# Connectors.net
KiCad netlist of a schematic drawn in Altium Designer
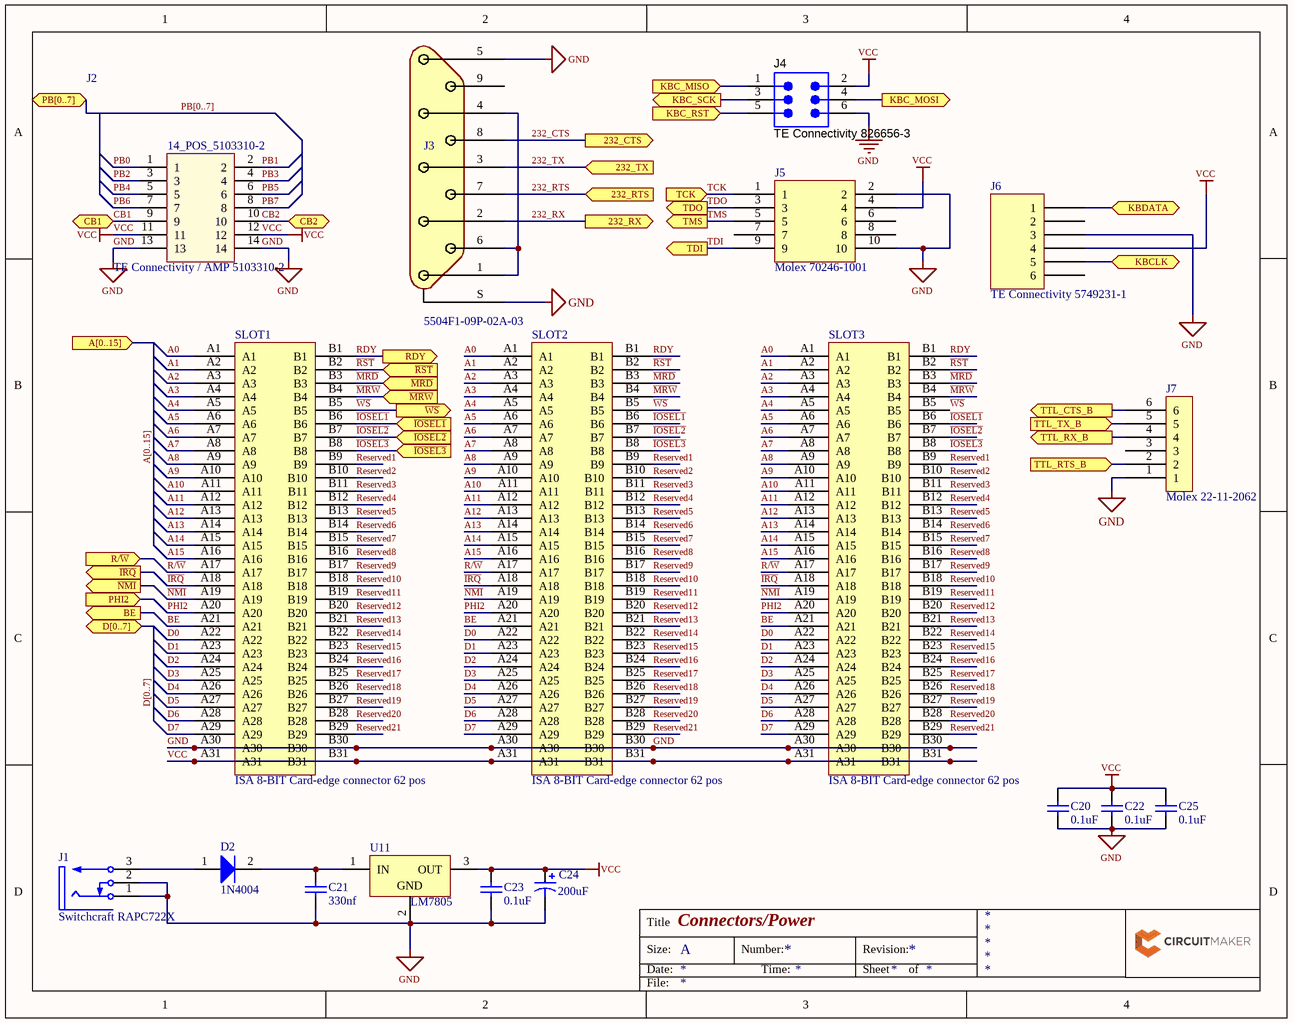
[diagram p0: Connectors.SchDoc]

(export (version "E")
  (design (tool "Eeschema 10.0.6"))
  (components
    (comp (ref "C20")
      (value "0.1uF")
      (footprint "CAPC1608X90X35NL15T15")
      (description "0603 0.1uF Capacitor")
      (libsource (lib "CommunityVault") (part "CAP-2"))
    )
    (comp (ref "C21")
      (value "330nf")
      (footprint "CAPC1608X90X35LL15T15")
      (description "CAP CER 0.33UF 16V 10% X5R 0603")
      (libsource (lib "CommunityVault") (part "CAP-2"))
    )
    (comp (ref "C22")
      (value "0.1uF")
      (footprint "CAPC1608X90X35NL15T15")
      (description "0603 0.1uF Capacitor")
      (libsource (lib "CommunityVault") (part "CAP-2"))
    )
    (comp (ref "C23")
      (value "0.1uF")
      (footprint "CAPC1608X90X35NL15T15")
      (description "0603 0.1uF Capacitor")
      (libsource (lib "CommunityVault") (part "CAP-2"))
    )
    (comp (ref "C24")
      (value "200uF")
      (footprint "PCB-3fis2k4xlpvnsk81kkhj-1")
      (fields (field (name "MANUFACTURER PART NUMBER") "ECA1CM102"))
      (libsource (lib "CommunityVault") (part "CMP-1635dc727a7cc9f2-2"))
    )
    (comp (ref "C25")
      (value "0.1uF")
      (footprint "CAPC1608X90X35NL15T15")
      (description "0603 0.1uF Capacitor")
      (libsource (lib "CommunityVault") (part "CAP-2"))
    )
    (comp (ref "D2")
      (value "1N4004")
      (footprint "DO-41")
      (description "1N400 Series 400 V 1 A Through Hole General Purpose Rectifier - DO-41")
      (libsource (lib "CommunityVault") (part "DIOD-A1K2-2"))
    )
    (comp (ref "J1")
      (value "Switchcraft RAPC722X")
      (footprint "PCB-1fbtkpzwj6p6nhvlt2g3-1")
      (description "Conn; AV; Power; Jack; Mini; 2.0mmPinDia; RtAngle; Thru-hole; forS760, S765Plug")
      (fields (field (name "MANUFACTURER PART NUMBER") "RAPC722X"))
      (libsource (lib "CommunityVault") (part "SYM-da391331d91005fe-1"))
    )
    (comp (ref "J2")
      (value "TE Connectivity / AMP 5103310-2")
      (footprint "PCB-04n3ni4juo6m1dp788kb-1")
      (description "Pin strip Contact spacing: 2.54 mm Total number of pins: 14 TE Connectivity 1 pc(s)")
      (libsource (lib "CommunityVault") (part "CMP-1a3bd16bc3bbc5fc-4"))
    )
    (comp (ref "J3")
      (value "5504F1-09P-02A-03")
      (footprint "PCB-jud4hregttv4p5s2mrjr-1")
      (libsource (lib "CommunityVault") (part "SYM-0794cfbf94bad853-2"))
    )
    (comp (ref "J4")
      (value "TE Connectivity 826656-3")
      (footprint "2X03")
      (fields (field (name "MANUFACTURER PART NUMBER") "826656-3"))
      (libsource (lib "CommunityVault") (part "Header_3x2"))
    )
    (comp (ref "J5")
      (value "Molex 70246-1001")
      (footprint "PCB-nsgmebcr356so910k4yq-1")
      (description "Conn Shrouded Header HDR 10 POS 2.54mm Solder ST Thru-Hole C-Grid???? Tray")
      (fields (field (name "MANUFACTURER PART NUMBER") "70246-1001"))
      (libsource (lib "CommunityVault") (part "CMP-470a8e03b20998cd-2"))
    )
    (comp (ref "J6")
      (value "TE Connectivity 5749231-1")
      (footprint "PCB-8pubcbuq08v906tmuwpg-1")
      (description "Conn Miniature Circular DIN RCP 6 POS Solder RA Thru-Hole 6 Terminal 1 Port Tube")
      (fields (field (name "MANUFACTURER PART NUMBER") "5749231-1"))
      (libsource (lib "CommunityVault") (part "CMP-b8aa73653b4d676d-4"))
    )
    (comp (ref "J7")
      (value "Molex 22-11-2062")
      (footprint "PCB-ioqv0i4y8bkpr9lvorvl-1")
      (description "KK® 254 Solid Header, Vertical, with Friction Lock, 6 Circuits, Gold (Au) Plating")
      (libsource (lib "CommunityVault") (part "SYM-4b8d8287433d944a-1"))
    )
    (comp (ref "SLOT1")
      (value "ISA 8-BIT Card-edge connector 62 pos")
      (footprint "PCB-80bthpdokcyhcgmko2pj-1")
      (description "62 pos card-edge connector")
      (libsource (lib "FavoritesLibrary") (part "SYM-pbfl1llzq4ddr18jwana-1"))
    )
    (comp (ref "SLOT2")
      (value "ISA 8-BIT Card-edge connector 62 pos")
      (footprint "PCB-80bthpdokcyhcgmko2pj-1")
      (description "62 pos card-edge connector")
      (libsource (lib "CommunityVault") (part "SYM-pbfl1llzq4ddr18jwana-1"))
    )
    (comp (ref "SLOT3")
      (value "ISA 8-BIT Card-edge connector 62 pos")
      (footprint "PCB-80bthpdokcyhcgmko2pj-1")
      (description "62 pos card-edge connector")
      (libsource (lib "CommunityVault") (part "SYM-pbfl1llzq4ddr18jwana-1"))
    )
    (comp (ref "U11")
      (value "LM7805")
      (footprint "PCB-6qghvgu276ezulagx1yw-1")
      (description "Linear Voltage Regulator, Positive, 5.0 V, 1.0 A Vout: 5.0 V; TJ = 0°C to +125°C")
      (libsource (lib "CommunityVault") (part "CMP-756abc604f31aaad-2"))
    )
  )
  (nets
    (net (code "1") (name "/232_CTS") (class "Default")
      (node (ref "J3") (pin "8") (pinfunction "8_8") (pintype "passive"))
    )
    (net (code "2") (name "/232_RTS") (class "Default")
      (node (ref "J3") (pin "7") (pinfunction "7_7") (pintype "passive"))
    )
    (net (code "3") (name "/232_RX") (class "Default")
      (node (ref "J3") (pin "2") (pinfunction "2_2") (pintype "passive"))
    )
    (net (code "4") (name "/232_TX") (class "Default")
      (node (ref "J3") (pin "3") (pinfunction "3_3") (pintype "passive"))
    )
    (net (code "5") (name "/A0") (class "Default")
      (node (ref "SLOT1") (pin "A1") (pinfunction "A1_A1") (pintype "passive"))
      (node (ref "SLOT2") (pin "A1") (pinfunction "A1_A1") (pintype "passive"))
      (node (ref "SLOT3") (pin "A1") (pinfunction "A1_A1") (pintype "passive"))
    )
    (net (code "6") (name "/A1") (class "Default")
      (node (ref "SLOT1") (pin "A2") (pinfunction "A2_A2") (pintype "passive"))
      (node (ref "SLOT2") (pin "A2") (pinfunction "A2_A2") (pintype "passive"))
      (node (ref "SLOT3") (pin "A2") (pinfunction "A2_A2") (pintype "passive"))
    )
    (net (code "7") (name "/A2") (class "Default")
      (node (ref "SLOT1") (pin "A3") (pinfunction "A3_A3") (pintype "passive"))
      (node (ref "SLOT2") (pin "A3") (pinfunction "A3_A3") (pintype "passive"))
      (node (ref "SLOT3") (pin "A3") (pinfunction "A3_A3") (pintype "passive"))
    )
    (net (code "8") (name "/A3") (class "Default")
      (node (ref "SLOT1") (pin "A4") (pinfunction "A4_A4") (pintype "passive"))
      (node (ref "SLOT2") (pin "A4") (pinfunction "A4_A4") (pintype "passive"))
      (node (ref "SLOT3") (pin "A4") (pinfunction "A4_A4") (pintype "passive"))
    )
    (net (code "9") (name "/A4") (class "Default")
      (node (ref "SLOT1") (pin "A5") (pinfunction "A5_A5") (pintype "passive"))
      (node (ref "SLOT2") (pin "A5") (pinfunction "A5_A5") (pintype "passive"))
      (node (ref "SLOT3") (pin "A5") (pinfunction "A5_A5") (pintype "passive"))
    )
    (net (code "10") (name "/A5") (class "Default")
      (node (ref "SLOT1") (pin "A6") (pinfunction "A6_A6") (pintype "passive"))
      (node (ref "SLOT2") (pin "A6") (pinfunction "A6_A6") (pintype "passive"))
      (node (ref "SLOT3") (pin "A6") (pinfunction "A6_A6") (pintype "passive"))
    )
    (net (code "11") (name "/A6") (class "Default")
      (node (ref "SLOT1") (pin "A7") (pinfunction "A7_A7") (pintype "passive"))
      (node (ref "SLOT2") (pin "A7") (pinfunction "A7_A7") (pintype "passive"))
      (node (ref "SLOT3") (pin "A7") (pinfunction "A7_A7") (pintype "passive"))
    )
    (net (code "12") (name "/A7") (class "Default")
      (node (ref "SLOT1") (pin "A8") (pinfunction "A8_A8") (pintype "passive"))
      (node (ref "SLOT2") (pin "A8") (pinfunction "A8_A8") (pintype "passive"))
      (node (ref "SLOT3") (pin "A8") (pinfunction "A8_A8") (pintype "passive"))
    )
    (net (code "13") (name "/A8") (class "Default")
      (node (ref "SLOT1") (pin "A9") (pinfunction "A9_A9") (pintype "passive"))
      (node (ref "SLOT2") (pin "A9") (pinfunction "A9_A9") (pintype "passive"))
      (node (ref "SLOT3") (pin "A9") (pinfunction "A9_A9") (pintype "passive"))
    )
    (net (code "14") (name "/A9") (class "Default")
      (node (ref "SLOT1") (pin "A10") (pinfunction "A10_A10") (pintype "passive"))
      (node (ref "SLOT2") (pin "A10") (pinfunction "A10_A10") (pintype "passive"))
      (node (ref "SLOT3") (pin "A10") (pinfunction "A10_A10") (pintype "passive"))
    )
    (net (code "15") (name "/A10") (class "Default")
      (node (ref "SLOT1") (pin "A11") (pinfunction "A11_A11") (pintype "passive"))
      (node (ref "SLOT2") (pin "A11") (pinfunction "A11_A11") (pintype "passive"))
      (node (ref "SLOT3") (pin "A11") (pinfunction "A11_A11") (pintype "passive"))
    )
    (net (code "16") (name "/A11") (class "Default")
      (node (ref "SLOT1") (pin "A12") (pinfunction "A12_A12") (pintype "passive"))
      (node (ref "SLOT2") (pin "A12") (pinfunction "A12_A12") (pintype "passive"))
      (node (ref "SLOT3") (pin "A12") (pinfunction "A12_A12") (pintype "passive"))
    )
    (net (code "17") (name "/A12") (class "Default")
      (node (ref "SLOT1") (pin "A13") (pinfunction "A13_A13") (pintype "passive"))
      (node (ref "SLOT2") (pin "A13") (pinfunction "A13_A13") (pintype "passive"))
      (node (ref "SLOT3") (pin "A13") (pinfunction "A13_A13") (pintype "passive"))
    )
    (net (code "18") (name "/A13") (class "Default")
      (node (ref "SLOT1") (pin "A14") (pinfunction "A14_A14") (pintype "passive"))
      (node (ref "SLOT2") (pin "A14") (pinfunction "A14_A14") (pintype "passive"))
      (node (ref "SLOT3") (pin "A14") (pinfunction "A14_A14") (pintype "passive"))
    )
    (net (code "19") (name "/A14") (class "Default")
      (node (ref "SLOT1") (pin "A15") (pinfunction "A15_A15") (pintype "passive"))
      (node (ref "SLOT2") (pin "A15") (pinfunction "A15_A15") (pintype "passive"))
      (node (ref "SLOT3") (pin "A15") (pinfunction "A15_A15") (pintype "passive"))
    )
    (net (code "20") (name "/A15") (class "Default")
      (node (ref "SLOT1") (pin "A16") (pinfunction "A16_A16") (pintype "passive"))
      (node (ref "SLOT2") (pin "A16") (pinfunction "A16_A16") (pintype "passive"))
      (node (ref "SLOT3") (pin "A16") (pinfunction "A16_A16") (pintype "passive"))
    )
    (net (code "22") (name "/BE") (class "Default")
      (node (ref "SLOT1") (pin "A21") (pinfunction "A21_A21") (pintype "passive"))
      (node (ref "SLOT2") (pin "A21") (pinfunction "A21_A21") (pintype "passive"))
      (node (ref "SLOT3") (pin "A21") (pinfunction "A21_A21") (pintype "passive"))
    )
    (net (code "23") (name "/CB1") (class "Default")
      (node (ref "J2") (pin "9") (pinfunction "9_9") (pintype "passive"))
    )
    (net (code "24") (name "/CB2") (class "Default")
      (node (ref "J2") (pin "10") (pinfunction "10_10") (pintype "passive"))
    )
    (net (code "25") (name "/D0") (class "Default")
      (node (ref "SLOT1") (pin "A22") (pinfunction "A22_A22") (pintype "passive"))
      (node (ref "SLOT2") (pin "A22") (pinfunction "A22_A22") (pintype "passive"))
      (node (ref "SLOT3") (pin "A22") (pinfunction "A22_A22") (pintype "passive"))
    )
    (net (code "26") (name "/D1") (class "Default")
      (node (ref "SLOT1") (pin "A23") (pinfunction "A23_A23") (pintype "passive"))
      (node (ref "SLOT2") (pin "A23") (pinfunction "A23_A23") (pintype "passive"))
      (node (ref "SLOT3") (pin "A23") (pinfunction "A23_A23") (pintype "passive"))
    )
    (net (code "27") (name "/D2") (class "Default")
      (node (ref "SLOT1") (pin "A24") (pinfunction "A24_A24") (pintype "passive"))
      (node (ref "SLOT2") (pin "A24") (pinfunction "A24_A24") (pintype "passive"))
      (node (ref "SLOT3") (pin "A24") (pinfunction "A24_A24") (pintype "passive"))
    )
    (net (code "28") (name "/D3") (class "Default")
      (node (ref "SLOT1") (pin "A25") (pinfunction "A25_A25") (pintype "passive"))
      (node (ref "SLOT2") (pin "A25") (pinfunction "A25_A25") (pintype "passive"))
      (node (ref "SLOT3") (pin "A25") (pinfunction "A25_A25") (pintype "passive"))
    )
    (net (code "29") (name "/D4") (class "Default")
      (node (ref "SLOT1") (pin "A26") (pinfunction "A26_A26") (pintype "passive"))
      (node (ref "SLOT2") (pin "A26") (pinfunction "A26_A26") (pintype "passive"))
      (node (ref "SLOT3") (pin "A26") (pinfunction "A26_A26") (pintype "passive"))
    )
    (net (code "30") (name "/D5") (class "Default")
      (node (ref "SLOT1") (pin "A27") (pinfunction "A27_A27") (pintype "passive"))
      (node (ref "SLOT2") (pin "A27") (pinfunction "A27_A27") (pintype "passive"))
      (node (ref "SLOT3") (pin "A27") (pinfunction "A27_A27") (pintype "passive"))
    )
    (net (code "31") (name "/D6") (class "Default")
      (node (ref "SLOT1") (pin "A28") (pinfunction "A28_A28") (pintype "passive"))
      (node (ref "SLOT2") (pin "A28") (pinfunction "A28_A28") (pintype "passive"))
      (node (ref "SLOT3") (pin "A28") (pinfunction "A28_A28") (pintype "passive"))
    )
    (net (code "32") (name "/D7") (class "Default")
      (node (ref "SLOT1") (pin "A29") (pinfunction "A29_A29") (pintype "passive"))
      (node (ref "SLOT2") (pin "A29") (pinfunction "A29_A29") (pintype "passive"))
      (node (ref "SLOT3") (pin "A29") (pinfunction "A29_A29") (pintype "passive"))
    )
    (net (code "34") (name "/KBCLK") (class "Default")
      (node (ref "J6") (pin "5") (pinfunction "5_5") (pintype "passive"))
    )
    (net (code "35") (name "/KBC_MISO") (class "Default")
      (node (ref "J4") (pin "1") (pinfunction "1_1") (pintype "passive"))
    )
    (net (code "36") (name "/KBC_MOSI") (class "Default")
      (node (ref "J4") (pin "4") (pinfunction "4_4") (pintype "passive"))
    )
    (net (code "37") (name "/KBC_RST") (class "Default")
      (node (ref "J4") (pin "5") (pinfunction "5_5") (pintype "passive"))
    )
    (net (code "38") (name "/KBC_SCK") (class "Default")
      (node (ref "J4") (pin "3") (pinfunction "3_3") (pintype "passive"))
    )
    (net (code "39") (name "/KBDATA") (class "Default")
      (node (ref "J6") (pin "1") (pinfunction "1_1") (pintype "passive"))
    )
    (net (code "40") (name "/PB0") (class "Default")
      (node (ref "J2") (pin "1") (pinfunction "1_1") (pintype "passive"))
    )
    (net (code "41") (name "/PB1") (class "Default")
      (node (ref "J2") (pin "2") (pinfunction "2_2") (pintype "passive"))
    )
    (net (code "42") (name "/PB2") (class "Default")
      (node (ref "J2") (pin "3") (pinfunction "3_3") (pintype "passive"))
    )
    (net (code "43") (name "/PB3") (class "Default")
      (node (ref "J2") (pin "4") (pinfunction "4_4") (pintype "passive"))
    )
    (net (code "44") (name "/PB4") (class "Default")
      (node (ref "J2") (pin "5") (pinfunction "5_5") (pintype "passive"))
    )
    (net (code "45") (name "/PB5") (class "Default")
      (node (ref "J2") (pin "6") (pinfunction "6_6") (pintype "passive"))
    )
    (net (code "46") (name "/PB6") (class "Default")
      (node (ref "J2") (pin "7") (pinfunction "7_7") (pintype "passive"))
    )
    (net (code "47") (name "/PB7") (class "Default")
      (node (ref "J2") (pin "8") (pinfunction "8_8") (pintype "passive"))
    )
    (net (code "49") (name "/PHI2") (class "Default")
      (node (ref "SLOT1") (pin "A20") (pinfunction "A20_A20") (pintype "passive"))
      (node (ref "SLOT2") (pin "A20") (pinfunction "A20_A20") (pintype "passive"))
      (node (ref "SLOT3") (pin "A20") (pinfunction "A20_A20") (pintype "passive"))
    )
    (net (code "50") (name "/RDY") (class "Default")
      (node (ref "SLOT1") (pin "B1") (pinfunction "B1_B1") (pintype "passive"))
      (node (ref "SLOT2") (pin "B1") (pinfunction "B1_B1") (pintype "passive"))
      (node (ref "SLOT3") (pin "B1") (pinfunction "B1_B1") (pintype "passive"))
    )
    (net (code "51") (name "/Reserved1") (class "Default")
      (node (ref "SLOT1") (pin "B9") (pinfunction "B9_B9") (pintype "passive"))
      (node (ref "SLOT2") (pin "B9") (pinfunction "B9_B9") (pintype "passive"))
      (node (ref "SLOT3") (pin "B9") (pinfunction "B9_B9") (pintype "passive"))
    )
    (net (code "52") (name "/Reserved2") (class "Default")
      (node (ref "SLOT1") (pin "B10") (pinfunction "B10_B10") (pintype "passive"))
      (node (ref "SLOT2") (pin "B10") (pinfunction "B10_B10") (pintype "passive"))
      (node (ref "SLOT3") (pin "B10") (pinfunction "B10_B10") (pintype "passive"))
    )
    (net (code "53") (name "/Reserved3") (class "Default")
      (node (ref "SLOT1") (pin "B11") (pinfunction "B11_B11") (pintype "passive"))
      (node (ref "SLOT2") (pin "B11") (pinfunction "B11_B11") (pintype "passive"))
      (node (ref "SLOT3") (pin "B11") (pinfunction "B11_B11") (pintype "passive"))
    )
    (net (code "54") (name "/Reserved4") (class "Default")
      (node (ref "SLOT1") (pin "B12") (pinfunction "B12_B12") (pintype "passive"))
      (node (ref "SLOT2") (pin "B12") (pinfunction "B12_B12") (pintype "passive"))
      (node (ref "SLOT3") (pin "B12") (pinfunction "B12_B12") (pintype "passive"))
    )
    (net (code "55") (name "/Reserved5") (class "Default")
      (node (ref "SLOT1") (pin "B13") (pinfunction "B13_B13") (pintype "passive"))
      (node (ref "SLOT2") (pin "B13") (pinfunction "B13_B13") (pintype "passive"))
      (node (ref "SLOT3") (pin "B13") (pinfunction "B13_B13") (pintype "passive"))
    )
    (net (code "56") (name "/Reserved6") (class "Default")
      (node (ref "SLOT1") (pin "B14") (pinfunction "B14_B14") (pintype "passive"))
      (node (ref "SLOT2") (pin "B14") (pinfunction "B14_B14") (pintype "passive"))
      (node (ref "SLOT3") (pin "B14") (pinfunction "B14_B14") (pintype "passive"))
    )
    (net (code "57") (name "/Reserved7") (class "Default")
      (node (ref "SLOT1") (pin "B15") (pinfunction "B15_B15") (pintype "passive"))
      (node (ref "SLOT2") (pin "B15") (pinfunction "B15_B15") (pintype "passive"))
      (node (ref "SLOT3") (pin "B15") (pinfunction "B15_B15") (pintype "passive"))
    )
    (net (code "58") (name "/Reserved8") (class "Default")
      (node (ref "SLOT1") (pin "B16") (pinfunction "B16_B16") (pintype "passive"))
      (node (ref "SLOT2") (pin "B16") (pinfunction "B16_B16") (pintype "passive"))
      (node (ref "SLOT3") (pin "B16") (pinfunction "B16_B16") (pintype "passive"))
    )
    (net (code "59") (name "/Reserved9") (class "Default")
      (node (ref "SLOT1") (pin "B17") (pinfunction "B17_B17") (pintype "passive"))
      (node (ref "SLOT2") (pin "B17") (pinfunction "B17_B17") (pintype "passive"))
      (node (ref "SLOT3") (pin "B17") (pinfunction "B17_B17") (pintype "passive"))
    )
    (net (code "60") (name "/Reserved10") (class "Default")
      (node (ref "SLOT1") (pin "B18") (pinfunction "B18_B18") (pintype "passive"))
      (node (ref "SLOT2") (pin "B18") (pinfunction "B18_B18") (pintype "passive"))
      (node (ref "SLOT3") (pin "B18") (pinfunction "B18_B18") (pintype "passive"))
    )
    (net (code "61") (name "/Reserved11") (class "Default")
      (node (ref "SLOT1") (pin "B19") (pinfunction "B19_B19") (pintype "passive"))
      (node (ref "SLOT2") (pin "B19") (pinfunction "B19_B19") (pintype "passive"))
      (node (ref "SLOT3") (pin "B19") (pinfunction "B19_B19") (pintype "passive"))
    )
    (net (code "62") (name "/Reserved12") (class "Default")
      (node (ref "SLOT1") (pin "B20") (pinfunction "B20_B20") (pintype "passive"))
      (node (ref "SLOT2") (pin "B20") (pinfunction "B20_B20") (pintype "passive"))
      (node (ref "SLOT3") (pin "B20") (pinfunction "B20_B20") (pintype "passive"))
    )
    (net (code "63") (name "/Reserved13") (class "Default")
      (node (ref "SLOT1") (pin "B21") (pinfunction "B21_B21") (pintype "passive"))
      (node (ref "SLOT2") (pin "B21") (pinfunction "B21_B21") (pintype "passive"))
      (node (ref "SLOT3") (pin "B21") (pinfunction "B21_B21") (pintype "passive"))
    )
    (net (code "64") (name "/Reserved14") (class "Default")
      (node (ref "SLOT1") (pin "B22") (pinfunction "B22_B22") (pintype "passive"))
      (node (ref "SLOT2") (pin "B22") (pinfunction "B22_B22") (pintype "passive"))
      (node (ref "SLOT3") (pin "B22") (pinfunction "B22_B22") (pintype "passive"))
    )
    (net (code "65") (name "/Reserved15") (class "Default")
      (node (ref "SLOT1") (pin "B23") (pinfunction "B23_B23") (pintype "passive"))
      (node (ref "SLOT2") (pin "B23") (pinfunction "B23_B23") (pintype "passive"))
      (node (ref "SLOT3") (pin "B23") (pinfunction "B23_B23") (pintype "passive"))
    )
    (net (code "66") (name "/Reserved16") (class "Default")
      (node (ref "SLOT1") (pin "B24") (pinfunction "B24_B24") (pintype "passive"))
      (node (ref "SLOT2") (pin "B24") (pinfunction "B24_B24") (pintype "passive"))
      (node (ref "SLOT3") (pin "B24") (pinfunction "B24_B24") (pintype "passive"))
    )
    (net (code "67") (name "/Reserved17") (class "Default")
      (node (ref "SLOT1") (pin "B25") (pinfunction "B25_B25") (pintype "passive"))
      (node (ref "SLOT2") (pin "B25") (pinfunction "B25_B25") (pintype "passive"))
      (node (ref "SLOT3") (pin "B25") (pinfunction "B25_B25") (pintype "passive"))
    )
    (net (code "68") (name "/Reserved18") (class "Default")
      (node (ref "SLOT1") (pin "B26") (pinfunction "B26_B26") (pintype "passive"))
      (node (ref "SLOT2") (pin "B26") (pinfunction "B26_B26") (pintype "passive"))
      (node (ref "SLOT3") (pin "B26") (pinfunction "B26_B26") (pintype "passive"))
    )
    (net (code "69") (name "/Reserved19") (class "Default")
      (node (ref "SLOT1") (pin "B27") (pinfunction "B27_B27") (pintype "passive"))
      (node (ref "SLOT2") (pin "B27") (pinfunction "B27_B27") (pintype "passive"))
      (node (ref "SLOT3") (pin "B27") (pinfunction "B27_B27") (pintype "passive"))
    )
    (net (code "70") (name "/Reserved20") (class "Default")
      (node (ref "SLOT1") (pin "B28") (pinfunction "B28_B28") (pintype "passive"))
      (node (ref "SLOT2") (pin "B28") (pinfunction "B28_B28") (pintype "passive"))
      (node (ref "SLOT3") (pin "B28") (pinfunction "B28_B28") (pintype "passive"))
    )
    (net (code "71") (name "/Reserved21") (class "Default")
      (node (ref "SLOT1") (pin "B29") (pinfunction "B29_B29") (pintype "passive"))
      (node (ref "SLOT2") (pin "B29") (pinfunction "B29_B29") (pintype "passive"))
      (node (ref "SLOT3") (pin "B29") (pinfunction "B29_B29") (pintype "passive"))
    )
    (net (code "72") (name "/R{slash}~{W}") (class "Default")
      (node (ref "SLOT1") (pin "A17") (pinfunction "A17_A17") (pintype "passive"))
      (node (ref "SLOT2") (pin "A17") (pinfunction "A17_A17") (pintype "passive"))
      (node (ref "SLOT3") (pin "A17") (pinfunction "A17_A17") (pintype "passive"))
    )
    (net (code "73") (name "/TCK") (class "Default")
      (node (ref "J5") (pin "1") (pinfunction "1_1") (pintype "passive"))
    )
    (net (code "74") (name "/TDI") (class "Default")
      (node (ref "J5") (pin "9") (pinfunction "9_9") (pintype "passive"))
    )
    (net (code "75") (name "/TDO") (class "Default")
      (node (ref "J5") (pin "3") (pinfunction "3_3") (pintype "passive"))
    )
    (net (code "76") (name "/TMS") (class "Default")
      (node (ref "J5") (pin "5") (pinfunction "5_5") (pintype "passive"))
    )
    (net (code "77") (name "/TTL_CTS_B") (class "Default")
      (node (ref "J7") (pin "6") (pinfunction "6_6") (pintype "passive"))
    )
    (net (code "78") (name "/TTL_RTS_B") (class "Default")
      (node (ref "J7") (pin "2") (pinfunction "2_2") (pintype "passive"))
    )
    (net (code "79") (name "/TTL_RX_B") (class "Default")
      (node (ref "J7") (pin "4") (pinfunction "4_4") (pintype "passive"))
    )
    (net (code "80") (name "/TTL_TX_B") (class "Default")
      (node (ref "J7") (pin "5") (pinfunction "5_5") (pintype "passive"))
    )
    (net (code "81") (name "/~{IOSEL1}") (class "Default")
      (node (ref "SLOT1") (pin "B6") (pinfunction "B6_B6") (pintype "passive"))
      (node (ref "SLOT2") (pin "B6") (pinfunction "B6_B6") (pintype "passive"))
      (node (ref "SLOT3") (pin "B6") (pinfunction "B6_B6") (pintype "passive"))
    )
    (net (code "82") (name "/~{IOSEL2}") (class "Default")
      (node (ref "SLOT1") (pin "B7") (pinfunction "B7_B7") (pintype "passive"))
      (node (ref "SLOT2") (pin "B7") (pinfunction "B7_B7") (pintype "passive"))
      (node (ref "SLOT3") (pin "B7") (pinfunction "B7_B7") (pintype "passive"))
    )
    (net (code "83") (name "/~{IOSEL3}") (class "Default")
      (node (ref "SLOT1") (pin "B8") (pinfunction "B8_B8") (pintype "passive"))
      (node (ref "SLOT2") (pin "B8") (pinfunction "B8_B8") (pintype "passive"))
      (node (ref "SLOT3") (pin "B8") (pinfunction "B8_B8") (pintype "passive"))
    )
    (net (code "84") (name "/~{IRQ}") (class "Default")
      (node (ref "SLOT1") (pin "A18") (pinfunction "A18_A18") (pintype "passive"))
      (node (ref "SLOT2") (pin "A18") (pinfunction "A18_A18") (pintype "passive"))
      (node (ref "SLOT3") (pin "A18") (pinfunction "A18_A18") (pintype "passive"))
    )
    (net (code "85") (name "/~{MRD}") (class "Default")
      (node (ref "SLOT1") (pin "B3") (pinfunction "B3_B3") (pintype "passive"))
      (node (ref "SLOT2") (pin "B3") (pinfunction "B3_B3") (pintype "passive"))
      (node (ref "SLOT3") (pin "B3") (pinfunction "B3_B3") (pintype "passive"))
    )
    (net (code "86") (name "/~{MRW}") (class "Default")
      (node (ref "SLOT1") (pin "B4") (pinfunction "B4_B4") (pintype "passive"))
      (node (ref "SLOT2") (pin "B4") (pinfunction "B4_B4") (pintype "passive"))
      (node (ref "SLOT3") (pin "B4") (pinfunction "B4_B4") (pintype "passive"))
    )
    (net (code "87") (name "/~{NMI}") (class "Default")
      (node (ref "SLOT1") (pin "A19") (pinfunction "A19_A19") (pintype "passive"))
      (node (ref "SLOT2") (pin "A19") (pinfunction "A19_A19") (pintype "passive"))
      (node (ref "SLOT3") (pin "A19") (pinfunction "A19_A19") (pintype "passive"))
    )
    (net (code "88") (name "/~{RST}") (class "Default")
      (node (ref "SLOT1") (pin "B2") (pinfunction "B2_B2") (pintype "passive"))
      (node (ref "SLOT2") (pin "B2") (pinfunction "B2_B2") (pintype "passive"))
      (node (ref "SLOT3") (pin "B2") (pinfunction "B2_B2") (pintype "passive"))
    )
    (net (code "89") (name "/~{WS}") (class "Default")
      (node (ref "SLOT1") (pin "B5") (pinfunction "B5_B5") (pintype "passive"))
      (node (ref "SLOT2") (pin "B5") (pinfunction "B5_B5") (pintype "passive"))
      (node (ref "SLOT3") (pin "B5") (pinfunction "B5_B5") (pintype "passive"))
    )
    (net (code "90") (name "GND") (class "Default")
      (node (ref "C20") (pin "2") (pinfunction "2_2") (pintype "passive"))
      (node (ref "C21") (pin "1") (pinfunction "1_1") (pintype "passive"))
      (node (ref "C22") (pin "2") (pinfunction "2_2") (pintype "passive"))
      (node (ref "C23") (pin "1") (pinfunction "1_1") (pintype "passive"))
      (node (ref "C24") (pin "2") (pinfunction "2_2") (pintype "passive"))
      (node (ref "C25") (pin "2") (pinfunction "2_2") (pintype "passive"))
      (node (ref "J1") (pin "1") (pinfunction "SLEEVE_1") (pintype "power_in"))
      (node (ref "J1") (pin "2") (pinfunction "SHUNT_2") (pintype "power_in"))
      (node (ref "J2") (pin "13") (pinfunction "13_13") (pintype "passive"))
      (node (ref "J2") (pin "14") (pinfunction "14_14") (pintype "passive"))
      (node (ref "J3") (pin "5") (pinfunction "5_5") (pintype "passive"))
      (node (ref "J3") (pin "S") (pinfunction "S_S") (pintype "passive"))
      (node (ref "J4") (pin "6") (pinfunction "6_6") (pintype "passive"))
      (node (ref "J5") (pin "10") (pinfunction "10_10") (pintype "passive"))
      (node (ref "J5") (pin "2") (pinfunction "2_2") (pintype "passive"))
      (node (ref "J6") (pin "3") (pinfunction "3_3") (pintype "passive"))
      (node (ref "J7") (pin "1") (pinfunction "1_1") (pintype "passive"))
      (node (ref "SLOT1") (pin "A30") (pinfunction "A30_A30") (pintype "passive"))
      (node (ref "SLOT1") (pin "B30") (pinfunction "B30_B30") (pintype "passive"))
      (node (ref "SLOT2") (pin "A30") (pinfunction "A30_A30") (pintype "passive"))
      (node (ref "SLOT2") (pin "B30") (pinfunction "B30_B30") (pintype "passive"))
      (node (ref "SLOT3") (pin "A30") (pinfunction "A30_A30") (pintype "passive"))
      (node (ref "SLOT3") (pin "B30") (pinfunction "B30_B30") (pintype "passive"))
      (node (ref "U11") (pin "2") (pinfunction "GND_2") (pintype "power_in"))
    )
    (net (code "91") (name "Net-(D2-+)") (class "Default")
      (node (ref "D2") (pin "1") (pinfunction "+_1") (pintype "passive"))
      (node (ref "J1") (pin "3") (pinfunction "TIP_3") (pintype "power_in"))
    )
    (net (code "92") (name "Net-(D2--)") (class "Default")
      (node (ref "C21") (pin "2") (pinfunction "2_2") (pintype "passive"))
      (node (ref "D2") (pin "2") (pinfunction "-_2") (pintype "passive"))
      (node (ref "U11") (pin "1") (pinfunction "IN_1") (pintype "power_in"))
    )
    (net (code "93") (name "Net-(J3-Pad1)") (class "Default")
      (node (ref "J3") (pin "1") (pinfunction "1_1") (pintype "passive"))
      (node (ref "J3") (pin "4") (pinfunction "4_4") (pintype "passive"))
      (node (ref "J3") (pin "6") (pinfunction "6_6") (pintype "passive"))
    )
    (net (code "94") (name "VCC") (class "Default")
      (node (ref "C20") (pin "1") (pinfunction "1_1") (pintype "passive"))
      (node (ref "C22") (pin "1") (pinfunction "1_1") (pintype "passive"))
      (node (ref "C23") (pin "2") (pinfunction "2_2") (pintype "passive"))
      (node (ref "C24") (pin "1") (pinfunction "1_1") (pintype "passive"))
      (node (ref "C25") (pin "1") (pinfunction "1_1") (pintype "passive"))
      (node (ref "J2") (pin "11") (pinfunction "11_11") (pintype "passive"))
      (node (ref "J2") (pin "12") (pinfunction "12_12") (pintype "passive"))
      (node (ref "J4") (pin "2") (pinfunction "2_2") (pintype "passive"))
      (node (ref "J5") (pin "4") (pinfunction "4_4") (pintype "passive"))
      (node (ref "J6") (pin "4") (pinfunction "4_4") (pintype "passive"))
      (node (ref "SLOT1") (pin "A31") (pinfunction "A31_A31") (pintype "passive"))
      (node (ref "SLOT1") (pin "B31") (pinfunction "B31_B31") (pintype "passive"))
      (node (ref "SLOT2") (pin "A31") (pinfunction "A31_A31") (pintype "passive"))
      (node (ref "SLOT2") (pin "B31") (pinfunction "B31_B31") (pintype "passive"))
      (node (ref "SLOT3") (pin "A31") (pinfunction "A31_A31") (pintype "passive"))
      (node (ref "SLOT3") (pin "B31") (pinfunction "B31_B31") (pintype "passive"))
      (node (ref "U11") (pin "3") (pinfunction "OUT_3") (pintype "power_in"))
    )
    (net (code "95") (name "unconnected-(J3-Pad9)") (class "Default")
      (node (ref "J3") (pin "9") (pinfunction "9_9") (pintype "passive"))
    )
    (net (code "96") (name "unconnected-(J5-Pad6)") (class "Default")
      (node (ref "J5") (pin "6") (pinfunction "6_6") (pintype "passive"))
    )
    (net (code "97") (name "unconnected-(J5-Pad7)") (class "Default")
      (node (ref "J5") (pin "7") (pinfunction "7_7") (pintype "passive"))
    )
    (net (code "98") (name "unconnected-(J5-Pad8)") (class "Default")
      (node (ref "J5") (pin "8") (pinfunction "8_8") (pintype "passive"))
    )
    (net (code "99") (name "unconnected-(J6-Pad2)") (class "Default")
      (node (ref "J6") (pin "2") (pinfunction "2_2") (pintype "passive"))
    )
    (net (code "100") (name "unconnected-(J6-Pad6)") (class "Default")
      (node (ref "J6") (pin "6") (pinfunction "6_6") (pintype "passive"))
    )
    (net (code "101") (name "unconnected-(J7-Pad3)") (class "Default")
      (node (ref "J7") (pin "3") (pinfunction "3_3") (pintype "passive"))
    )
  )
)
